# ir.net
KiCad netlist of a schematic drawn in Altium Designer
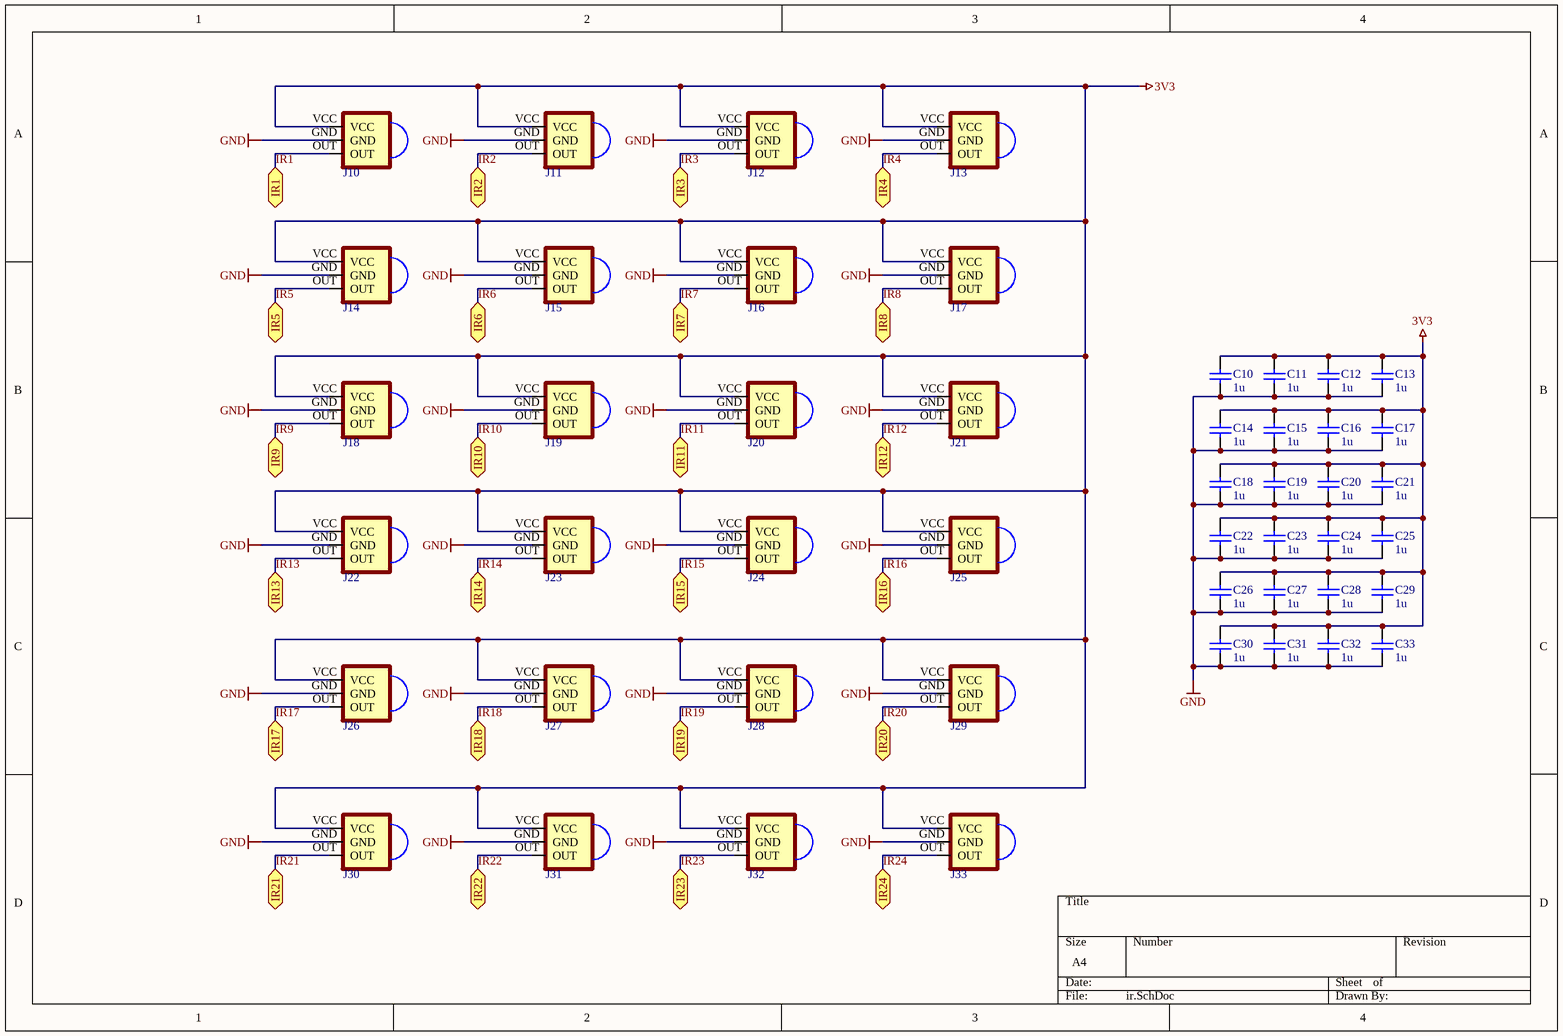
[diagram p0: ir.SchDoc]

(export (version "E")
  (design (tool "Eeschema 10.0.6"))
  (components
    (comp (ref "C10")
      (value "1u")
      (footprint "CAP0603")
      (description "0603 Capacitor")
      (libsource (lib "Integrated_Library1") (part "CAP0603"))
    )
    (comp (ref "C11")
      (value "1u")
      (footprint "CAP0603")
      (description "0603 Capacitor")
      (libsource (lib "Integrated_Library1") (part "CAP0603"))
    )
    (comp (ref "C12")
      (value "1u")
      (footprint "CAP0603")
      (description "0603 Capacitor")
      (libsource (lib "Integrated_Library1") (part "CAP0603"))
    )
    (comp (ref "C13")
      (value "1u")
      (footprint "CAP0603")
      (description "0603 Capacitor")
      (libsource (lib "Integrated_Library1") (part "CAP0603"))
    )
    (comp (ref "C14")
      (value "1u")
      (footprint "CAP0603")
      (description "0603 Capacitor")
      (libsource (lib "Integrated_Library1") (part "CAP0603"))
    )
    (comp (ref "C15")
      (value "1u")
      (footprint "CAP0603")
      (description "0603 Capacitor")
      (libsource (lib "Integrated_Library1") (part "CAP0603"))
    )
    (comp (ref "C16")
      (value "1u")
      (footprint "CAP0603")
      (description "0603 Capacitor")
      (libsource (lib "Integrated_Library1") (part "CAP0603"))
    )
    (comp (ref "C17")
      (value "1u")
      (footprint "CAP0603")
      (description "0603 Capacitor")
      (libsource (lib "Integrated_Library1") (part "CAP0603"))
    )
    (comp (ref "C18")
      (value "1u")
      (footprint "CAP0603")
      (description "0603 Capacitor")
      (libsource (lib "Integrated_Library1") (part "CAP0603"))
    )
    (comp (ref "C19")
      (value "1u")
      (footprint "CAP0603")
      (description "0603 Capacitor")
      (libsource (lib "Integrated_Library1") (part "CAP0603"))
    )
    (comp (ref "C20")
      (value "1u")
      (footprint "CAP0603")
      (description "0603 Capacitor")
      (libsource (lib "Integrated_Library1") (part "CAP0603"))
    )
    (comp (ref "C21")
      (value "1u")
      (footprint "CAP0603")
      (description "0603 Capacitor")
      (libsource (lib "Integrated_Library1") (part "CAP0603"))
    )
    (comp (ref "C22")
      (value "1u")
      (footprint "CAP0603")
      (description "0603 Capacitor")
      (libsource (lib "Integrated_Library1") (part "CAP0603"))
    )
    (comp (ref "C23")
      (value "1u")
      (footprint "CAP0603")
      (description "0603 Capacitor")
      (libsource (lib "Integrated_Library1") (part "CAP0603"))
    )
    (comp (ref "C24")
      (value "1u")
      (footprint "CAP0603")
      (description "0603 Capacitor")
      (libsource (lib "Integrated_Library1") (part "CAP0603"))
    )
    (comp (ref "C25")
      (value "1u")
      (footprint "CAP0603")
      (description "0603 Capacitor")
      (libsource (lib "Integrated_Library1") (part "CAP0603"))
    )
    (comp (ref "C26")
      (value "1u")
      (footprint "CAP0603")
      (description "0603 Capacitor")
      (libsource (lib "Integrated_Library1") (part "CAP0603"))
    )
    (comp (ref "C27")
      (value "1u")
      (footprint "CAP0603")
      (description "0603 Capacitor")
      (libsource (lib "Integrated_Library1") (part "CAP0603"))
    )
    (comp (ref "C28")
      (value "1u")
      (footprint "CAP0603")
      (description "0603 Capacitor")
      (libsource (lib "Integrated_Library1") (part "CAP0603"))
    )
    (comp (ref "C29")
      (value "1u")
      (footprint "CAP0603")
      (description "0603 Capacitor")
      (libsource (lib "Integrated_Library1") (part "CAP0603"))
    )
    (comp (ref "C30")
      (value "1u")
      (footprint "CAP0603")
      (description "0603 Capacitor")
      (libsource (lib "Integrated_Library1") (part "CAP0603"))
    )
    (comp (ref "C31")
      (value "1u")
      (footprint "CAP0603")
      (description "0603 Capacitor")
      (libsource (lib "Integrated_Library1") (part "CAP0603"))
    )
    (comp (ref "C32")
      (value "1u")
      (footprint "CAP0603")
      (description "0603 Capacitor")
      (libsource (lib "Integrated_Library1") (part "CAP0603"))
    )
    (comp (ref "C33")
      (value "1u")
      (footprint "CAP0603")
      (description "0603 Capacitor")
      (libsource (lib "Integrated_Library1") (part "CAP0603"))
    )
    (comp (ref "J10")
      (value "TSSP58038")
      (footprint "TSSP58038")
      (description "38 kHz 25 m 45° 5.5 V Through Hole IR Receiver Module for Light Barrier Systems")
      (fields (field (name "MF") "Vishay"))
      (libsource (lib "Hwa Chong Institution") (part "TSSP58038"))
    )
    (comp (ref "J11")
      (value "TSSP58038")
      (footprint "TSSP58038")
      (description "38 kHz 25 m 45° 5.5 V Through Hole IR Receiver Module for Light Barrier Systems")
      (fields (field (name "MF") "Vishay"))
      (libsource (lib "Hwa Chong Institution") (part "TSSP58038"))
    )
    (comp (ref "J12")
      (value "TSSP58038")
      (footprint "TSSP58038")
      (description "38 kHz 25 m 45° 5.5 V Through Hole IR Receiver Module for Light Barrier Systems")
      (fields (field (name "MF") "Vishay"))
      (libsource (lib "Hwa Chong Institution") (part "TSSP58038"))
    )
    (comp (ref "J13")
      (value "TSSP58038")
      (footprint "TSSP58038")
      (description "38 kHz 25 m 45° 5.5 V Through Hole IR Receiver Module for Light Barrier Systems")
      (fields (field (name "MF") "Vishay"))
      (libsource (lib "Hwa Chong Institution") (part "TSSP58038"))
    )
    (comp (ref "J14")
      (value "TSSP58038")
      (footprint "TSSP58038")
      (description "38 kHz 25 m 45° 5.5 V Through Hole IR Receiver Module for Light Barrier Systems")
      (fields (field (name "MF") "Vishay"))
      (libsource (lib "Hwa Chong Institution") (part "TSSP58038"))
    )
    (comp (ref "J15")
      (value "TSSP58038")
      (footprint "TSSP58038")
      (description "38 kHz 25 m 45° 5.5 V Through Hole IR Receiver Module for Light Barrier Systems")
      (fields (field (name "MF") "Vishay"))
      (libsource (lib "Hwa Chong Institution") (part "TSSP58038"))
    )
    (comp (ref "J16")
      (value "TSSP58038")
      (footprint "TSSP58038")
      (description "38 kHz 25 m 45° 5.5 V Through Hole IR Receiver Module for Light Barrier Systems")
      (fields (field (name "MF") "Vishay"))
      (libsource (lib "Hwa Chong Institution") (part "TSSP58038"))
    )
    (comp (ref "J17")
      (value "TSSP58038")
      (footprint "TSSP58038")
      (description "38 kHz 25 m 45° 5.5 V Through Hole IR Receiver Module for Light Barrier Systems")
      (fields (field (name "MF") "Vishay"))
      (libsource (lib "Hwa Chong Institution") (part "TSSP58038"))
    )
    (comp (ref "J18")
      (value "TSSP58038")
      (footprint "TSSP58038")
      (description "38 kHz 25 m 45° 5.5 V Through Hole IR Receiver Module for Light Barrier Systems")
      (fields (field (name "MF") "Vishay"))
      (libsource (lib "Hwa Chong Institution") (part "TSSP58038"))
    )
    (comp (ref "J19")
      (value "TSSP58038")
      (footprint "TSSP58038")
      (description "38 kHz 25 m 45° 5.5 V Through Hole IR Receiver Module for Light Barrier Systems")
      (fields (field (name "MF") "Vishay"))
      (libsource (lib "Hwa Chong Institution") (part "TSSP58038"))
    )
    (comp (ref "J20")
      (value "TSSP58038")
      (footprint "TSSP58038")
      (description "38 kHz 25 m 45° 5.5 V Through Hole IR Receiver Module for Light Barrier Systems")
      (fields (field (name "MF") "Vishay"))
      (libsource (lib "Hwa Chong Institution") (part "TSSP58038"))
    )
    (comp (ref "J21")
      (value "TSSP58038")
      (footprint "TSSP58038")
      (description "38 kHz 25 m 45° 5.5 V Through Hole IR Receiver Module for Light Barrier Systems")
      (fields (field (name "MF") "Vishay"))
      (libsource (lib "Hwa Chong Institution") (part "TSSP58038"))
    )
    (comp (ref "J22")
      (value "TSSP58038")
      (footprint "TSSP58038")
      (description "38 kHz 25 m 45° 5.5 V Through Hole IR Receiver Module for Light Barrier Systems")
      (fields (field (name "MF") "Vishay"))
      (libsource (lib "Hwa Chong Institution") (part "TSSP58038"))
    )
    (comp (ref "J23")
      (value "TSSP58038")
      (footprint "TSSP58038")
      (description "38 kHz 25 m 45° 5.5 V Through Hole IR Receiver Module for Light Barrier Systems")
      (fields (field (name "MF") "Vishay"))
      (libsource (lib "Hwa Chong Institution") (part "TSSP58038"))
    )
    (comp (ref "J24")
      (value "TSSP58038")
      (footprint "TSSP58038")
      (description "38 kHz 25 m 45° 5.5 V Through Hole IR Receiver Module for Light Barrier Systems")
      (fields (field (name "MF") "Vishay"))
      (libsource (lib "Hwa Chong Institution") (part "TSSP58038"))
    )
    (comp (ref "J25")
      (value "TSSP58038")
      (footprint "TSSP58038")
      (description "38 kHz 25 m 45° 5.5 V Through Hole IR Receiver Module for Light Barrier Systems")
      (fields (field (name "MF") "Vishay"))
      (libsource (lib "Hwa Chong Institution") (part "TSSP58038"))
    )
    (comp (ref "J26")
      (value "TSSP58038")
      (footprint "TSSP58038")
      (description "38 kHz 25 m 45° 5.5 V Through Hole IR Receiver Module for Light Barrier Systems")
      (fields (field (name "MF") "Vishay"))
      (libsource (lib "Hwa Chong Institution") (part "TSSP58038"))
    )
    (comp (ref "J27")
      (value "TSSP58038")
      (footprint "TSSP58038")
      (description "38 kHz 25 m 45° 5.5 V Through Hole IR Receiver Module for Light Barrier Systems")
      (fields (field (name "MF") "Vishay"))
      (libsource (lib "Hwa Chong Institution") (part "TSSP58038"))
    )
    (comp (ref "J28")
      (value "TSSP58038")
      (footprint "TSSP58038")
      (description "38 kHz 25 m 45° 5.5 V Through Hole IR Receiver Module for Light Barrier Systems")
      (fields (field (name "MF") "Vishay"))
      (libsource (lib "Hwa Chong Institution") (part "TSSP58038"))
    )
    (comp (ref "J29")
      (value "TSSP58038")
      (footprint "TSSP58038")
      (description "38 kHz 25 m 45° 5.5 V Through Hole IR Receiver Module for Light Barrier Systems")
      (fields (field (name "MF") "Vishay"))
      (libsource (lib "Hwa Chong Institution") (part "TSSP58038"))
    )
    (comp (ref "J30")
      (value "TSSP58038")
      (footprint "TSSP58038")
      (description "38 kHz 25 m 45° 5.5 V Through Hole IR Receiver Module for Light Barrier Systems")
      (fields (field (name "MF") "Vishay"))
      (libsource (lib "Hwa Chong Institution") (part "TSSP58038"))
    )
    (comp (ref "J31")
      (value "TSSP58038")
      (footprint "TSSP58038")
      (description "38 kHz 25 m 45° 5.5 V Through Hole IR Receiver Module for Light Barrier Systems")
      (fields (field (name "MF") "Vishay"))
      (libsource (lib "Hwa Chong Institution") (part "TSSP58038"))
    )
    (comp (ref "J32")
      (value "TSSP58038")
      (footprint "TSSP58038")
      (description "38 kHz 25 m 45° 5.5 V Through Hole IR Receiver Module for Light Barrier Systems")
      (fields (field (name "MF") "Vishay"))
      (libsource (lib "Hwa Chong Institution") (part "TSSP58038"))
    )
    (comp (ref "J33")
      (value "TSSP58038")
      (footprint "TSSP58038")
      (description "38 kHz 25 m 45° 5.5 V Through Hole IR Receiver Module for Light Barrier Systems")
      (fields (field (name "MF") "Vishay"))
      (libsource (lib "Hwa Chong Institution") (part "TSSP58038"))
    )
  )
  (nets
    (net (code "1") (name "/IR1") (class "Default")
      (node (ref "J10") (pin "OUT") (pinfunction "OUT_OUT") (pintype "bidirectional"))
    )
    (net (code "2") (name "/IR2") (class "Default")
      (node (ref "J11") (pin "OUT") (pinfunction "OUT_OUT") (pintype "bidirectional"))
    )
    (net (code "3") (name "/IR3") (class "Default")
      (node (ref "J12") (pin "OUT") (pinfunction "OUT_OUT") (pintype "bidirectional"))
    )
    (net (code "4") (name "/IR4") (class "Default")
      (node (ref "J13") (pin "OUT") (pinfunction "OUT_OUT") (pintype "bidirectional"))
    )
    (net (code "5") (name "/IR5") (class "Default")
      (node (ref "J14") (pin "OUT") (pinfunction "OUT_OUT") (pintype "bidirectional"))
    )
    (net (code "6") (name "/IR6") (class "Default")
      (node (ref "J15") (pin "OUT") (pinfunction "OUT_OUT") (pintype "bidirectional"))
    )
    (net (code "7") (name "/IR7") (class "Default")
      (node (ref "J16") (pin "OUT") (pinfunction "OUT_OUT") (pintype "bidirectional"))
    )
    (net (code "8") (name "/IR8") (class "Default")
      (node (ref "J17") (pin "OUT") (pinfunction "OUT_OUT") (pintype "bidirectional"))
    )
    (net (code "9") (name "/IR9") (class "Default")
      (node (ref "J18") (pin "OUT") (pinfunction "OUT_OUT") (pintype "bidirectional"))
    )
    (net (code "10") (name "/IR10") (class "Default")
      (node (ref "J19") (pin "OUT") (pinfunction "OUT_OUT") (pintype "bidirectional"))
    )
    (net (code "11") (name "/IR11") (class "Default")
      (node (ref "J20") (pin "OUT") (pinfunction "OUT_OUT") (pintype "bidirectional"))
    )
    (net (code "12") (name "/IR12") (class "Default")
      (node (ref "J21") (pin "OUT") (pinfunction "OUT_OUT") (pintype "bidirectional"))
    )
    (net (code "13") (name "/IR13") (class "Default")
      (node (ref "J22") (pin "OUT") (pinfunction "OUT_OUT") (pintype "bidirectional"))
    )
    (net (code "14") (name "/IR14") (class "Default")
      (node (ref "J23") (pin "OUT") (pinfunction "OUT_OUT") (pintype "bidirectional"))
    )
    (net (code "15") (name "/IR15") (class "Default")
      (node (ref "J24") (pin "OUT") (pinfunction "OUT_OUT") (pintype "bidirectional"))
    )
    (net (code "16") (name "/IR16") (class "Default")
      (node (ref "J25") (pin "OUT") (pinfunction "OUT_OUT") (pintype "bidirectional"))
    )
    (net (code "17") (name "/IR17") (class "Default")
      (node (ref "J26") (pin "OUT") (pinfunction "OUT_OUT") (pintype "bidirectional"))
    )
    (net (code "18") (name "/IR18") (class "Default")
      (node (ref "J27") (pin "OUT") (pinfunction "OUT_OUT") (pintype "bidirectional"))
    )
    (net (code "19") (name "/IR19") (class "Default")
      (node (ref "J28") (pin "OUT") (pinfunction "OUT_OUT") (pintype "bidirectional"))
    )
    (net (code "20") (name "/IR20") (class "Default")
      (node (ref "J29") (pin "OUT") (pinfunction "OUT_OUT") (pintype "bidirectional"))
    )
    (net (code "21") (name "/IR21") (class "Default")
      (node (ref "J30") (pin "OUT") (pinfunction "OUT_OUT") (pintype "bidirectional"))
    )
    (net (code "22") (name "/IR22") (class "Default")
      (node (ref "J31") (pin "OUT") (pinfunction "OUT_OUT") (pintype "bidirectional"))
    )
    (net (code "23") (name "/IR23") (class "Default")
      (node (ref "J32") (pin "OUT") (pinfunction "OUT_OUT") (pintype "bidirectional"))
    )
    (net (code "24") (name "/IR24") (class "Default")
      (node (ref "J33") (pin "OUT") (pinfunction "OUT_OUT") (pintype "bidirectional"))
    )
    (net (code "25") (name "3V3") (class "Default")
      (node (ref "C10") (pin "2") (pinfunction "2_2") (pintype "passive"))
      (node (ref "C11") (pin "2") (pinfunction "2_2") (pintype "passive"))
      (node (ref "C12") (pin "2") (pinfunction "2_2") (pintype "passive"))
      (node (ref "C13") (pin "2") (pinfunction "2_2") (pintype "passive"))
      (node (ref "C14") (pin "2") (pinfunction "2_2") (pintype "passive"))
      (node (ref "C15") (pin "2") (pinfunction "2_2") (pintype "passive"))
      (node (ref "C16") (pin "2") (pinfunction "2_2") (pintype "passive"))
      (node (ref "C17") (pin "2") (pinfunction "2_2") (pintype "passive"))
      (node (ref "C18") (pin "2") (pinfunction "2_2") (pintype "passive"))
      (node (ref "C19") (pin "2") (pinfunction "2_2") (pintype "passive"))
      (node (ref "C20") (pin "2") (pinfunction "2_2") (pintype "passive"))
      (node (ref "C21") (pin "2") (pinfunction "2_2") (pintype "passive"))
      (node (ref "C22") (pin "2") (pinfunction "2_2") (pintype "passive"))
      (node (ref "C23") (pin "2") (pinfunction "2_2") (pintype "passive"))
      (node (ref "C24") (pin "2") (pinfunction "2_2") (pintype "passive"))
      (node (ref "C25") (pin "2") (pinfunction "2_2") (pintype "passive"))
      (node (ref "C26") (pin "2") (pinfunction "2_2") (pintype "passive"))
      (node (ref "C27") (pin "2") (pinfunction "2_2") (pintype "passive"))
      (node (ref "C28") (pin "2") (pinfunction "2_2") (pintype "passive"))
      (node (ref "C29") (pin "2") (pinfunction "2_2") (pintype "passive"))
      (node (ref "C30") (pin "2") (pinfunction "2_2") (pintype "passive"))
      (node (ref "C31") (pin "2") (pinfunction "2_2") (pintype "passive"))
      (node (ref "C32") (pin "2") (pinfunction "2_2") (pintype "passive"))
      (node (ref "C33") (pin "2") (pinfunction "2_2") (pintype "passive"))
      (node (ref "J10") (pin "VCC") (pinfunction "VCC_VCC") (pintype "power_in"))
      (node (ref "J11") (pin "VCC") (pinfunction "VCC_VCC") (pintype "power_in"))
      (node (ref "J12") (pin "VCC") (pinfunction "VCC_VCC") (pintype "power_in"))
      (node (ref "J13") (pin "VCC") (pinfunction "VCC_VCC") (pintype "power_in"))
      (node (ref "J14") (pin "VCC") (pinfunction "VCC_VCC") (pintype "power_in"))
      (node (ref "J15") (pin "VCC") (pinfunction "VCC_VCC") (pintype "power_in"))
      (node (ref "J16") (pin "VCC") (pinfunction "VCC_VCC") (pintype "power_in"))
      (node (ref "J17") (pin "VCC") (pinfunction "VCC_VCC") (pintype "power_in"))
      (node (ref "J18") (pin "VCC") (pinfunction "VCC_VCC") (pintype "power_in"))
      (node (ref "J19") (pin "VCC") (pinfunction "VCC_VCC") (pintype "power_in"))
      (node (ref "J20") (pin "VCC") (pinfunction "VCC_VCC") (pintype "power_in"))
      (node (ref "J21") (pin "VCC") (pinfunction "VCC_VCC") (pintype "power_in"))
      (node (ref "J22") (pin "VCC") (pinfunction "VCC_VCC") (pintype "power_in"))
      (node (ref "J23") (pin "VCC") (pinfunction "VCC_VCC") (pintype "power_in"))
      (node (ref "J24") (pin "VCC") (pinfunction "VCC_VCC") (pintype "power_in"))
      (node (ref "J25") (pin "VCC") (pinfunction "VCC_VCC") (pintype "power_in"))
      (node (ref "J26") (pin "VCC") (pinfunction "VCC_VCC") (pintype "power_in"))
      (node (ref "J27") (pin "VCC") (pinfunction "VCC_VCC") (pintype "power_in"))
      (node (ref "J28") (pin "VCC") (pinfunction "VCC_VCC") (pintype "power_in"))
      (node (ref "J29") (pin "VCC") (pinfunction "VCC_VCC") (pintype "power_in"))
      (node (ref "J30") (pin "VCC") (pinfunction "VCC_VCC") (pintype "power_in"))
      (node (ref "J31") (pin "VCC") (pinfunction "VCC_VCC") (pintype "power_in"))
      (node (ref "J32") (pin "VCC") (pinfunction "VCC_VCC") (pintype "power_in"))
      (node (ref "J33") (pin "VCC") (pinfunction "VCC_VCC") (pintype "power_in"))
    )
    (net (code "26") (name "GND") (class "Default")
      (node (ref "C10") (pin "1") (pinfunction "1_1") (pintype "passive"))
      (node (ref "C11") (pin "1") (pinfunction "1_1") (pintype "passive"))
      (node (ref "C12") (pin "1") (pinfunction "1_1") (pintype "passive"))
      (node (ref "C13") (pin "1") (pinfunction "1_1") (pintype "passive"))
      (node (ref "C14") (pin "1") (pinfunction "1_1") (pintype "passive"))
      (node (ref "C15") (pin "1") (pinfunction "1_1") (pintype "passive"))
      (node (ref "C16") (pin "1") (pinfunction "1_1") (pintype "passive"))
      (node (ref "C17") (pin "1") (pinfunction "1_1") (pintype "passive"))
      (node (ref "C18") (pin "1") (pinfunction "1_1") (pintype "passive"))
      (node (ref "C19") (pin "1") (pinfunction "1_1") (pintype "passive"))
      (node (ref "C20") (pin "1") (pinfunction "1_1") (pintype "passive"))
      (node (ref "C21") (pin "1") (pinfunction "1_1") (pintype "passive"))
      (node (ref "C22") (pin "1") (pinfunction "1_1") (pintype "passive"))
      (node (ref "C23") (pin "1") (pinfunction "1_1") (pintype "passive"))
      (node (ref "C24") (pin "1") (pinfunction "1_1") (pintype "passive"))
      (node (ref "C25") (pin "1") (pinfunction "1_1") (pintype "passive"))
      (node (ref "C26") (pin "1") (pinfunction "1_1") (pintype "passive"))
      (node (ref "C27") (pin "1") (pinfunction "1_1") (pintype "passive"))
      (node (ref "C28") (pin "1") (pinfunction "1_1") (pintype "passive"))
      (node (ref "C29") (pin "1") (pinfunction "1_1") (pintype "passive"))
      (node (ref "C30") (pin "1") (pinfunction "1_1") (pintype "passive"))
      (node (ref "C31") (pin "1") (pinfunction "1_1") (pintype "passive"))
      (node (ref "C32") (pin "1") (pinfunction "1_1") (pintype "passive"))
      (node (ref "C33") (pin "1") (pinfunction "1_1") (pintype "passive"))
      (node (ref "J10") (pin "GND") (pinfunction "GND_GND") (pintype "power_in"))
      (node (ref "J11") (pin "GND") (pinfunction "GND_GND") (pintype "power_in"))
      (node (ref "J12") (pin "GND") (pinfunction "GND_GND") (pintype "power_in"))
      (node (ref "J13") (pin "GND") (pinfunction "GND_GND") (pintype "power_in"))
      (node (ref "J14") (pin "GND") (pinfunction "GND_GND") (pintype "power_in"))
      (node (ref "J15") (pin "GND") (pinfunction "GND_GND") (pintype "power_in"))
      (node (ref "J16") (pin "GND") (pinfunction "GND_GND") (pintype "power_in"))
      (node (ref "J17") (pin "GND") (pinfunction "GND_GND") (pintype "power_in"))
      (node (ref "J18") (pin "GND") (pinfunction "GND_GND") (pintype "power_in"))
      (node (ref "J19") (pin "GND") (pinfunction "GND_GND") (pintype "power_in"))
      (node (ref "J20") (pin "GND") (pinfunction "GND_GND") (pintype "power_in"))
      (node (ref "J21") (pin "GND") (pinfunction "GND_GND") (pintype "power_in"))
      (node (ref "J22") (pin "GND") (pinfunction "GND_GND") (pintype "power_in"))
      (node (ref "J23") (pin "GND") (pinfunction "GND_GND") (pintype "power_in"))
      (node (ref "J24") (pin "GND") (pinfunction "GND_GND") (pintype "power_in"))
      (node (ref "J25") (pin "GND") (pinfunction "GND_GND") (pintype "power_in"))
      (node (ref "J26") (pin "GND") (pinfunction "GND_GND") (pintype "power_in"))
      (node (ref "J27") (pin "GND") (pinfunction "GND_GND") (pintype "power_in"))
      (node (ref "J28") (pin "GND") (pinfunction "GND_GND") (pintype "power_in"))
      (node (ref "J29") (pin "GND") (pinfunction "GND_GND") (pintype "power_in"))
      (node (ref "J30") (pin "GND") (pinfunction "GND_GND") (pintype "power_in"))
      (node (ref "J31") (pin "GND") (pinfunction "GND_GND") (pintype "power_in"))
      (node (ref "J32") (pin "GND") (pinfunction "GND_GND") (pintype "power_in"))
      (node (ref "J33") (pin "GND") (pinfunction "GND_GND") (pintype "power_in"))
    )
  )
)
